# Relay.net
KiCad netlist of a schematic drawn in Altium Designer
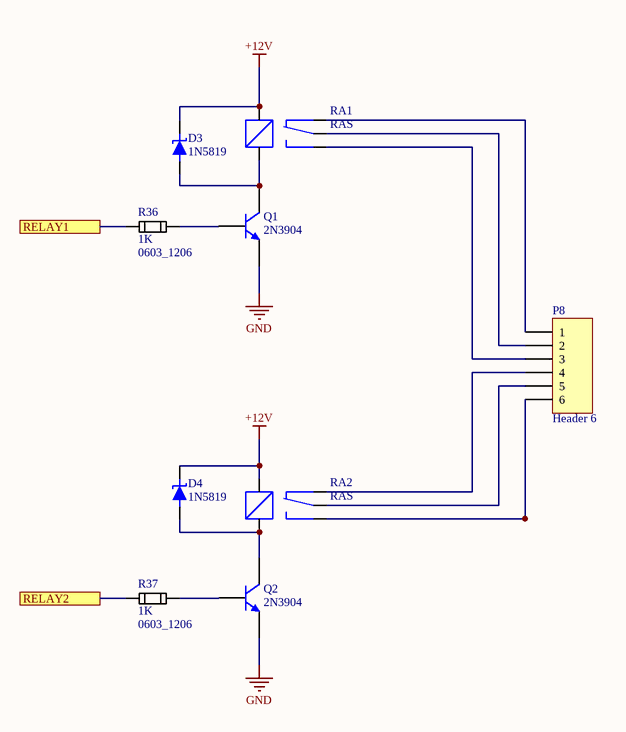
[diagram p0: Relay.SchDoc]

(export (version "E")
  (design (tool "Eeschema 10.0.6"))
  (components
    (comp (ref "D3")
      (value "1N5819")
      (footprint "DO-41-300")
      (description "40V 1A")
      (libsource (lib "Diodes-Power") (part "1N5819"))
    )
    (comp (ref "D4")
      (value "1N5819")
      (footprint "DO-41-300")
      (description "40V 1A")
      (libsource (lib "Diodes-Power") (part "1N5819"))
    )
    (comp (ref "P8")
      (value "Header 6")
      (footprint "KF2EDGV/R-6P")
      (description "Header, 6-Pin")
      (fields (field (name "PUBLISHER") "Altium Limited"))
      (libsource (lib "Miscellaneous Connectors") (part "Header 6"))
    )
    (comp (ref "Q1")
      (value "2N3904")
      (footprint "TO-92A-Pitch100MILS")
      (description "NPN General Purpose Amplifier")
      (fields (field (name "PUBLISHER") "Altium Limited"))
      (libsource (lib "THTransistor") (part "2N3904"))
    )
    (comp (ref "Q2")
      (value "2N3904")
      (footprint "TO-92A-Pitch100MILS")
      (description "NPN General Purpose Amplifier")
      (fields (field (name "PUBLISHER") "Altium Limited"))
      (libsource (lib "THTransistor") (part "2N3904"))
    )
    (comp (ref "R36")
      (value "1K")
      (footprint "SMD_CHIP_RESISTOR_0603_TO_1206")
      (description "SMD_CHIP_RESISTOR_0603_TO_1206")
      (fields (field (name "ALTIUM_VALUE") "0603_1206"))
      (libsource (lib "SMDResistors") (part "SMD_CHIP_RESISTOR_0603_TO_1206"))
    )
    (comp (ref "R37")
      (value "1K")
      (footprint "SMD_CHIP_RESISTOR_0603_TO_1206")
      (description "SMD_CHIP_RESISTOR_0603_TO_1206")
      (fields (field (name "ALTIUM_VALUE") "0603_1206"))
      (libsource (lib "SMDResistors") (part "SMD_CHIP_RESISTOR_0603_TO_1206"))
    )
    (comp (ref "RA1")
      (value "RAS")
      (footprint "Rele RAS")
      (description "AC-120V 15A DC-14V 20A 30V 15A /0.36W")
      (libsource (lib "Devise") (part "Relay RAS"))
    )
    (comp (ref "RA2")
      (value "RAS")
      (footprint "Rele RAS")
      (description "AC-120V 15A DC-14V 20A 30V 15A /0.36W")
      (libsource (lib "Devise") (part "Relay RAS"))
    )
  )
  (nets
    (net (code "1") (name "+12V") (class "Default")
      (node (ref "D3") (pin "2") (pinfunction "K_2") (pintype "passive"))
      (node (ref "D4") (pin "2") (pinfunction "K_2") (pintype "passive"))
      (node (ref "RA1") (pin "1") (pinfunction "a_1") (pintype "passive"))
      (node (ref "RA2") (pin "1") (pinfunction "a_1") (pintype "passive"))
    )
    (net (code "2") (name "/RELAY1") (class "Default")
      (node (ref "R36") (pin "2") (pinfunction "2_2") (pintype "passive"))
    )
    (net (code "3") (name "/RELAY2") (class "Default")
      (node (ref "R37") (pin "2") (pinfunction "2_2") (pintype "passive"))
    )
    (net (code "4") (name "GND") (class "Default")
      (node (ref "Q1") (pin "1") (pinfunction "E_1") (pintype "passive"))
      (node (ref "Q2") (pin "1") (pinfunction "E_1") (pintype "passive"))
    )
    (net (code "5") (name "Net-(D3-A)") (class "Default")
      (node (ref "D3") (pin "1") (pinfunction "A_1") (pintype "passive"))
      (node (ref "Q1") (pin "3") (pinfunction "C_3") (pintype "passive"))
      (node (ref "RA1") (pin "2") (pinfunction "b_2") (pintype "passive"))
    )
    (net (code "6") (name "Net-(D4-A)") (class "Default")
      (node (ref "D4") (pin "1") (pinfunction "A_1") (pintype "passive"))
      (node (ref "Q2") (pin "3") (pinfunction "C_3") (pintype "passive"))
      (node (ref "RA2") (pin "2") (pinfunction "b_2") (pintype "passive"))
    )
    (net (code "7") (name "Net-(Q1-B)") (class "Default")
      (node (ref "Q1") (pin "2") (pinfunction "B_2") (pintype "passive"))
      (node (ref "R36") (pin "1") (pinfunction "1_1") (pintype "passive"))
    )
    (net (code "8") (name "Net-(Q2-B)") (class "Default")
      (node (ref "Q2") (pin "2") (pinfunction "B_2") (pintype "passive"))
      (node (ref "R37") (pin "1") (pinfunction "1_1") (pintype "passive"))
    )
    (net (code "9") (name "Net-(RA1-NC)") (class "Default")
      (node (ref "P8") (pin "1") (pinfunction "1_1") (pintype "passive"))
      (node (ref "RA1") (pin "3") (pinfunction "NC_3") (pintype "passive"))
    )
    (net (code "10") (name "Net-(RA1-NO)") (class "Default")
      (node (ref "P8") (pin "3") (pinfunction "3_3") (pintype "passive"))
      (node (ref "RA1") (pin "5") (pinfunction "NO_5") (pintype "passive"))
    )
    (net (code "11") (name "Net-(RA1-O)") (class "Default")
      (node (ref "P8") (pin "2") (pinfunction "2_2") (pintype "passive"))
      (node (ref "RA1") (pin "4") (pinfunction "O_4") (pintype "passive"))
    )
    (net (code "12") (name "Net-(RA2-NC)") (class "Default")
      (node (ref "P8") (pin "4") (pinfunction "4_4") (pintype "passive"))
      (node (ref "RA2") (pin "3") (pinfunction "NC_3") (pintype "passive"))
    )
    (net (code "13") (name "Net-(RA2-NO)") (class "Default")
      (node (ref "P8") (pin "6") (pinfunction "6_6") (pintype "passive"))
      (node (ref "RA2") (pin "5") (pinfunction "NO_5") (pintype "passive"))
    )
    (net (code "14") (name "Net-(RA2-O)") (class "Default")
      (node (ref "P8") (pin "5") (pinfunction "5_5") (pintype "passive"))
      (node (ref "RA2") (pin "4") (pinfunction "O_4") (pintype "passive"))
    )
  )
)
